# AC_mains_Sensing.net
KiCad netlist of a schematic drawn in Altium Designer
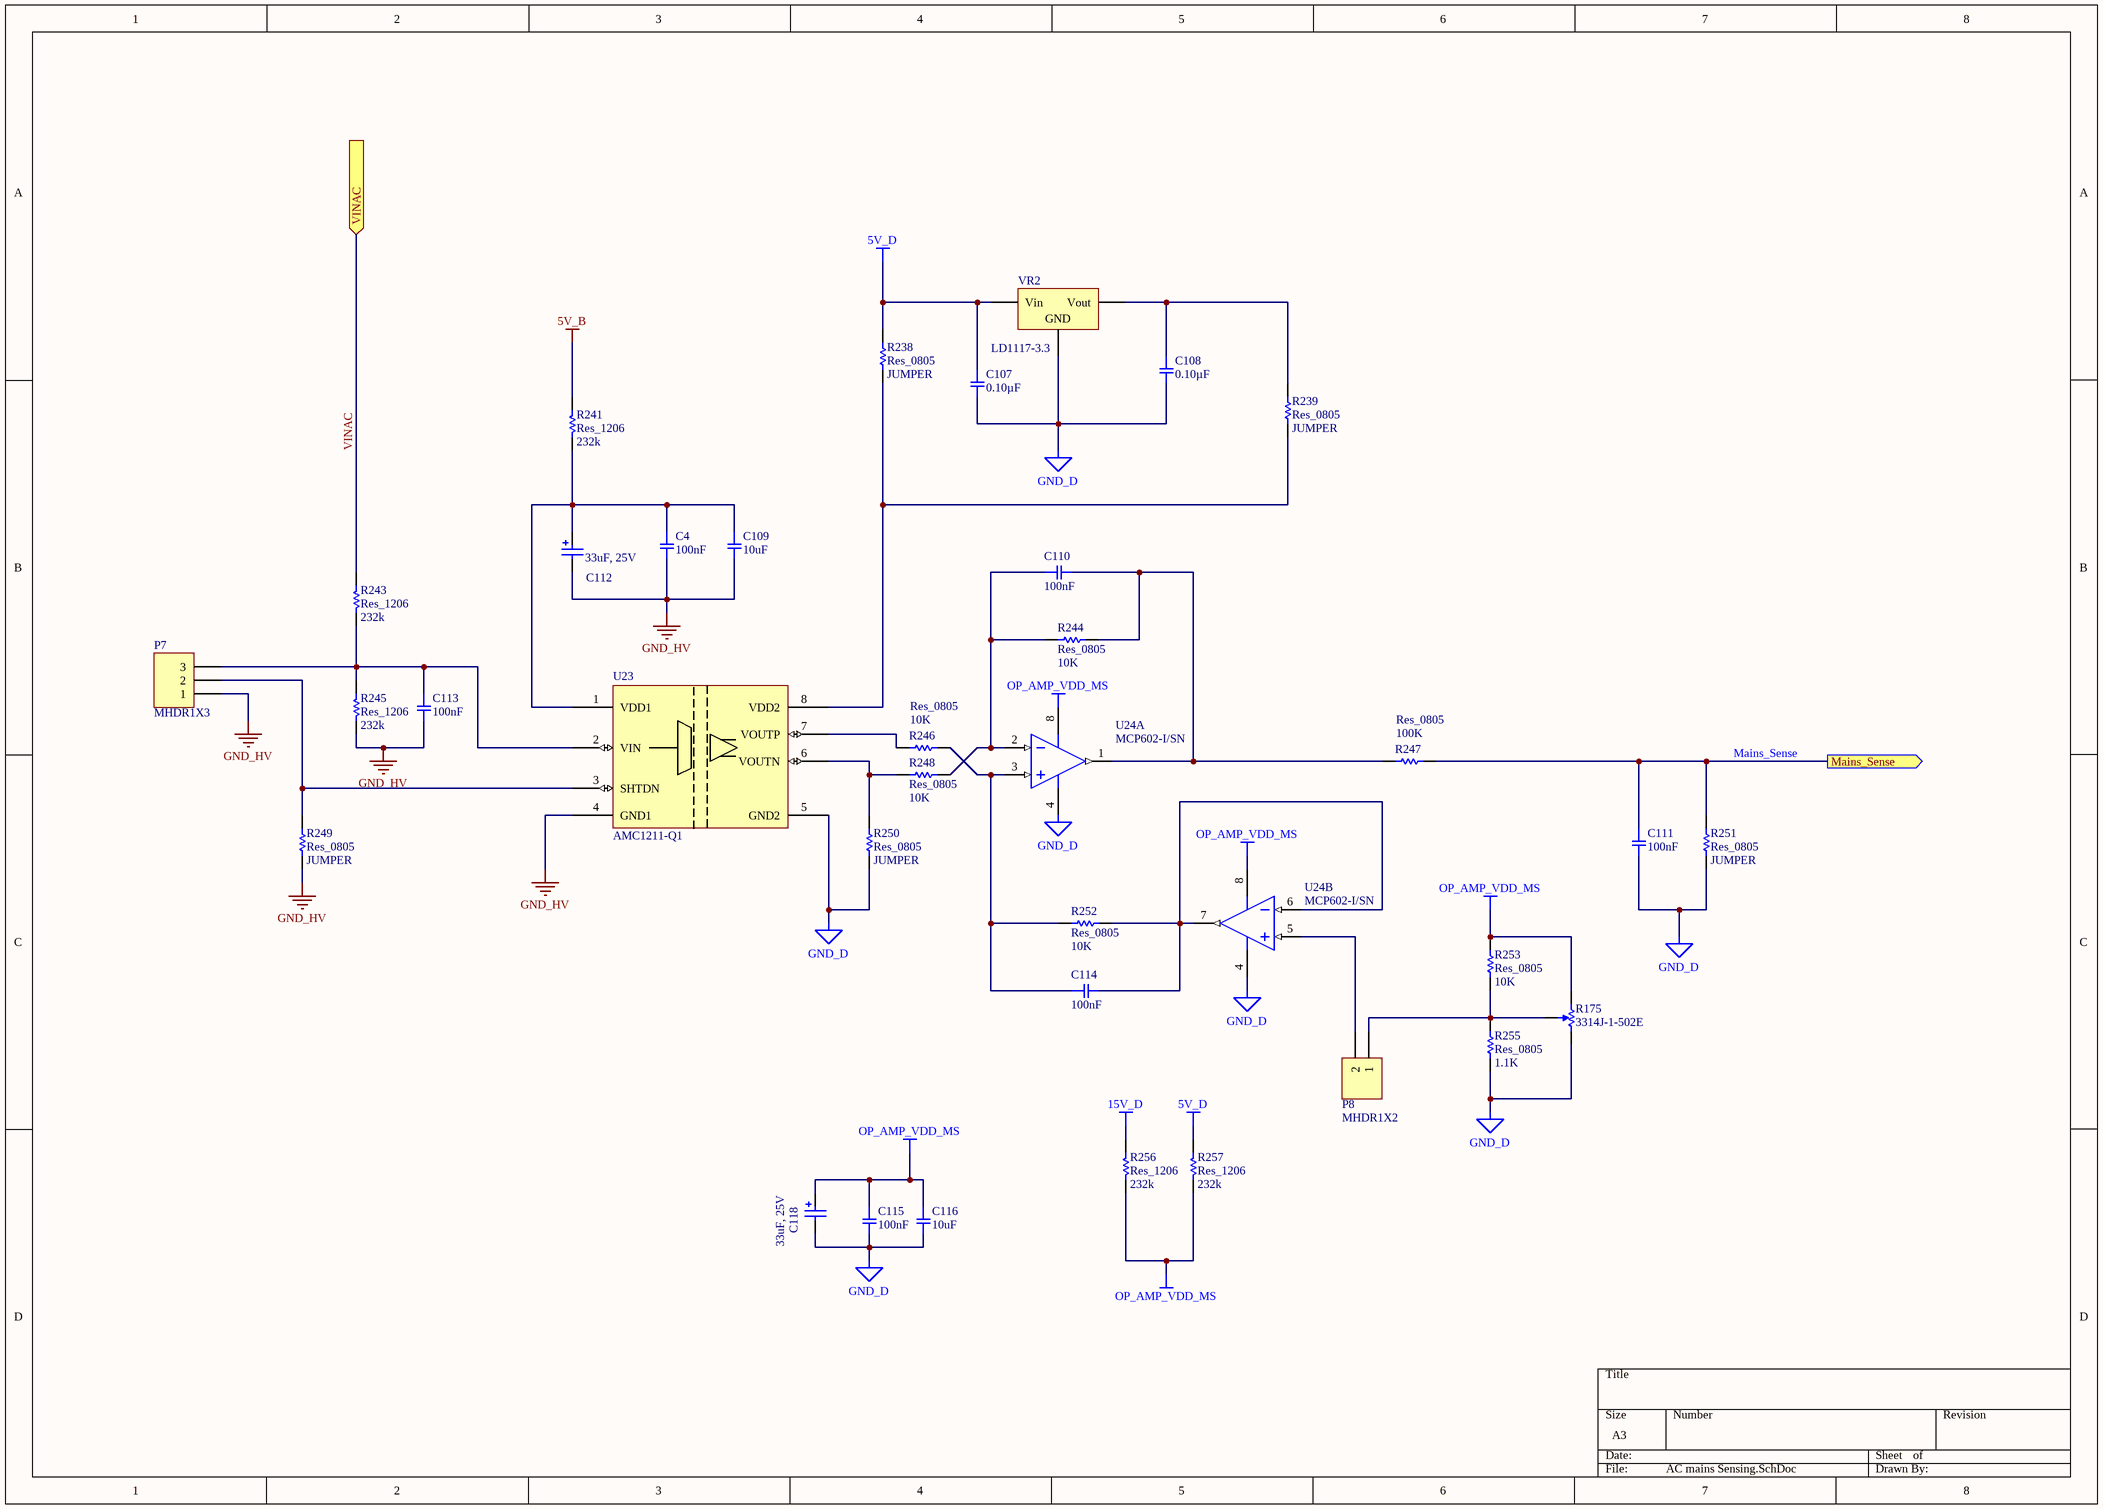
[diagram p0: AC mains Sensing.SchDoc]

(export (version "E")
  (design (tool "Eeschema 10.0.6"))
  (components
    (comp (ref "C4")
      (value "100nF")
      (footprint "SMD-0805C")
      (description "CAP CER 10000PF 250V X7T 0805")
      (fields
        (field (name "DIGI-KEY PART NUMBER") "490-13986-1-ND")
        (field (name "PART NUMBER") "GC321AD72E103KX01D")
      )
      (libsource (lib "capacitor_murata_0805") (part "GC321AD72E103KX01D"))
    )
    (comp (ref "C107")
      (value "0.10µF")
      (footprint "SMD-0805C")
      (description "CAP CER 0.1UF 50V X7R 0805")
      (fields
        (field (name "DIGI-KEY PART NUMBER") "490-11955-1-ND")
        (field (name "PART NUMBER") "GCD21BR71H104KA01L")
      )
      (libsource (lib "capacitor_murata_0805") (part "GCD21BR71H104KA01L"))
    )
    (comp (ref "C108")
      (value "0.10µF")
      (footprint "SMD-0805C")
      (description "CAP CER 0.1UF 50V X7R 0805")
      (fields
        (field (name "DIGI-KEY PART NUMBER") "490-11955-1-ND")
        (field (name "PART NUMBER") "GCD21BR71H104KA01L")
      )
      (libsource (lib "capacitor_murata_0805") (part "GCD21BR71H104KA01L"))
    )
    (comp (ref "C109")
      (value "10uF")
      (footprint "SMD-0805C")
      (description "CAP CER 10000PF 250V X7T 0805")
      (fields
        (field (name "DIGI-KEY PART NUMBER") "490-13986-1-ND")
        (field (name "PART NUMBER") "GC321AD72E103KX01D")
      )
      (libsource (lib "capacitor_murata_0805") (part "GC321AD72E103KX01D"))
    )
    (comp (ref "C110")
      (value "100nF")
      (footprint "SMD-0805C")
      (description "CAP CER 10000PF 250V X7T 0805")
      (fields
        (field (name "DIGI-KEY PART NUMBER") "490-13986-1-ND")
        (field (name "PART NUMBER") "GC321AD72E103KX01D")
      )
      (libsource (lib "capacitor_murata_0805") (part "GC321AD72E103KX01D"))
    )
    (comp (ref "C111")
      (value "100nF")
      (footprint "SMD-0805C")
      (description "CAP CER 10000PF 250V X7T 0805")
      (fields
        (field (name "DIGI-KEY PART NUMBER") "490-13986-1-ND")
        (field (name "PART NUMBER") "GC321AD72E103KX01D")
      )
      (libsource (lib "capacitor_murata_0805") (part "GC321AD72E103KX01D"))
    )
    (comp (ref "C112")
      (value "33uF, 25V")
      (footprint "WCAP-ASLL_6.3x5.5")
      (description "WCAP-ASLL SMT Aluminum Electrolytic Capacitors, D6.3mm x L5.5mm, 33uF, +/-20%, 25VDC")
      (fields (field (name "PART NUMBER") "865060443003") (field (name "PUBLISHER") "Wurth Elektronik"))
      (libsource (lib "Altium_WCAP-ASLL_SMD") (part "865060443003"))
    )
    (comp (ref "C113")
      (value "100nF")
      (footprint "SMD-0805C")
      (description "CAP CER 10000PF 250V X7T 0805")
      (fields
        (field (name "DIGI-KEY PART NUMBER") "490-13986-1-ND")
        (field (name "PART NUMBER") "GC321AD72E103KX01D")
      )
      (libsource (lib "capacitor_murata_0805") (part "GC321AD72E103KX01D"))
    )
    (comp (ref "C114")
      (value "100nF")
      (footprint "SMD-0805C")
      (description "CAP CER 10000PF 250V X7T 0805")
      (fields
        (field (name "DIGI-KEY PART NUMBER") "490-13986-1-ND")
        (field (name "PART NUMBER") "GC321AD72E103KX01D")
      )
      (libsource (lib "capacitor_murata_0805") (part "GC321AD72E103KX01D"))
    )
    (comp (ref "C115")
      (value "100nF")
      (footprint "SMD-0805C")
      (description "CAP CER 10000PF 250V X7T 0805")
      (fields
        (field (name "DIGI-KEY PART NUMBER") "490-13986-1-ND")
        (field (name "PART NUMBER") "GC321AD72E103KX01D")
      )
      (libsource (lib "capacitor_murata_0805") (part "GC321AD72E103KX01D"))
    )
    (comp (ref "C116")
      (value "10uF")
      (footprint "SMD-0805C")
      (description "CAP CER 10000PF 250V X7T 0805")
      (fields
        (field (name "DIGI-KEY PART NUMBER") "490-13986-1-ND")
        (field (name "PART NUMBER") "GC321AD72E103KX01D")
      )
      (libsource (lib "capacitor_murata_0805") (part "GC321AD72E103KX01D"))
    )
    (comp (ref "C118")
      (value "33uF, 25V")
      (footprint "WCAP-ASLL_6.3x5.5")
      (description "WCAP-ASLL SMT Aluminum Electrolytic Capacitors, D6.3mm x L5.5mm, 33uF, +/-20%, 25VDC")
      (fields (field (name "PART NUMBER") "865060443003") (field (name "PUBLISHER") "Wurth Elektronik"))
      (libsource (lib "Altium_WCAP-ASLL_SMD") (part "865060443003"))
    )
    (comp (ref "P7")
      (value "MHDR1X3")
      (footprint "MHDR1X3")
      (description "Header, 3-Pin")
      (fields (field (name "PUBLISHER") "Altium Limited"))
      (libsource (lib "Miscellaneous Connectors") (part "MHDR1X3"))
    )
    (comp (ref "P8")
      (value "MHDR1X2")
      (footprint "61900211121")
      (description "Header, 2-Pin")
      (fields (field (name "PUBLISHER") "Altium Limited"))
      (libsource (lib "Miscellaneous Connectors") (part "MHDR1X2"))
    )
    (comp (ref "R175")
      (value "3314J-1-502E")
      (footprint "BOUR-3314J-1_V")
      (fields
        (field (name "POWER") "250")
        (field (name "MANUFACTURER") "Bourns")
        (field (name "TOLERANCE") "±20%")
      )
      (libsource (lib "Altium Content Vault") (part "RES-ADJ-3_A"))
    )
    (comp (ref "R238")
      (value "Res_0805")
      (footprint "WRIS-KSKE_0805_H=0.6mm")
      (description "Resistor")
      (fields (field (name "ALTIUM_VALUE") "JUMPER") (field (name "PUBLISHER") "Altium Limited"))
      (libsource (lib "Miscellaneous Devices") (part "Res1"))
    )
    (comp (ref "R239")
      (value "Res_0805")
      (footprint "WRIS-KSKE_0805_H=0.6mm")
      (description "Resistor")
      (fields (field (name "ALTIUM_VALUE") "JUMPER") (field (name "PUBLISHER") "Altium Limited"))
      (libsource (lib "Miscellaneous Devices") (part "Res1"))
    )
    (comp (ref "R241")
      (value "Res_1206")
      (footprint "WRIS-KSKE_1206_H=0.6mm")
      (description "Resistor")
      (fields (field (name "ALTIUM_VALUE") "232k") (field (name "PUBLISHER") "Altium Limited"))
      (libsource (lib "Miscellaneous Devices") (part "Res1"))
    )
    (comp (ref "R243")
      (value "Res_1206")
      (footprint "WRIS-KSKE_1206_H=0.6mm")
      (description "Resistor")
      (fields (field (name "ALTIUM_VALUE") "232k") (field (name "PUBLISHER") "Altium Limited"))
      (libsource (lib "Miscellaneous Devices") (part "Res1"))
    )
    (comp (ref "R244")
      (value "Res_0805")
      (footprint "WRIS-KSKE_0805_H=0.6mm")
      (description "Resistor")
      (fields (field (name "ALTIUM_VALUE") "10K") (field (name "PUBLISHER") "Altium Limited"))
      (libsource (lib "Miscellaneous Devices") (part "Res1"))
    )
    (comp (ref "R245")
      (value "Res_1206")
      (footprint "WRIS-KSKE_1206_H=0.6mm")
      (description "Resistor")
      (fields (field (name "ALTIUM_VALUE") "232k") (field (name "PUBLISHER") "Altium Limited"))
      (libsource (lib "Miscellaneous Devices") (part "Res1"))
    )
    (comp (ref "R246")
      (value "Res_0805")
      (footprint "WRIS-KSKE_0805_H=0.6mm")
      (description "Resistor")
      (fields (field (name "ALTIUM_VALUE") "10K") (field (name "PUBLISHER") "Altium Limited"))
      (libsource (lib "Miscellaneous Devices") (part "Res1"))
    )
    (comp (ref "R247")
      (value "Res_0805")
      (footprint "WRIS-KSKE_0805_H=0.6mm")
      (description "Resistor")
      (fields (field (name "ALTIUM_VALUE") "100K") (field (name "PUBLISHER") "Altium Limited"))
      (libsource (lib "Miscellaneous Devices") (part "Res1"))
    )
    (comp (ref "R248")
      (value "Res_0805")
      (footprint "WRIS-KSKE_0805_H=0.6mm")
      (description "Resistor")
      (fields (field (name "ALTIUM_VALUE") "10K") (field (name "PUBLISHER") "Altium Limited"))
      (libsource (lib "Miscellaneous Devices") (part "Res1"))
    )
    (comp (ref "R249")
      (value "Res_0805")
      (footprint "WRIS-KSKE_0805_H=0.6mm")
      (description "Resistor")
      (fields (field (name "ALTIUM_VALUE") "JUMPER") (field (name "PUBLISHER") "Altium Limited"))
      (libsource (lib "Miscellaneous Devices") (part "Res1"))
    )
    (comp (ref "R250")
      (value "Res_0805")
      (footprint "WRIS-KSKE_0805_H=0.6mm")
      (description "Resistor")
      (fields (field (name "ALTIUM_VALUE") "JUMPER") (field (name "PUBLISHER") "Altium Limited"))
      (libsource (lib "Miscellaneous Devices") (part "Res1"))
    )
    (comp (ref "R251")
      (value "Res_0805")
      (footprint "WRIS-KSKE_0805_H=0.6mm")
      (description "Resistor")
      (fields (field (name "ALTIUM_VALUE") "JUMPER") (field (name "PUBLISHER") "Altium Limited"))
      (libsource (lib "Miscellaneous Devices") (part "Res1"))
    )
    (comp (ref "R252")
      (value "Res_0805")
      (footprint "WRIS-KSKE_0805_H=0.6mm")
      (description "Resistor")
      (fields (field (name "ALTIUM_VALUE") "10K") (field (name "PUBLISHER") "Altium Limited"))
      (libsource (lib "Miscellaneous Devices") (part "Res1"))
    )
    (comp (ref "R253")
      (value "Res_0805")
      (footprint "WRIS-KSKE_0805_H=0.6mm")
      (description "Resistor")
      (fields (field (name "ALTIUM_VALUE") "10K") (field (name "PUBLISHER") "Altium Limited"))
      (libsource (lib "Miscellaneous Devices") (part "Res1"))
    )
    (comp (ref "R255")
      (value "Res_0805")
      (footprint "WRIS-KSKE_0805_H=0.6mm")
      (description "Resistor")
      (fields (field (name "ALTIUM_VALUE") "1.1K") (field (name "PUBLISHER") "Altium Limited"))
      (libsource (lib "Miscellaneous Devices") (part "Res1"))
    )
    (comp (ref "R256")
      (value "Res_1206")
      (footprint "WRIS-KSKE_1206_H=0.6mm")
      (description "Resistor")
      (fields (field (name "ALTIUM_VALUE") "232k") (field (name "PUBLISHER") "Altium Limited"))
      (libsource (lib "Miscellaneous Devices") (part "Res1"))
    )
    (comp (ref "R257")
      (value "Res_1206")
      (footprint "WRIS-KSKE_1206_H=0.6mm")
      (description "Resistor")
      (fields (field (name "ALTIUM_VALUE") "232k") (field (name "PUBLISHER") "Altium Limited"))
      (libsource (lib "Miscellaneous Devices") (part "Res1"))
    )
    (comp (ref "U23")
      (value "AMC1211-Q1")
      (footprint "SOIC127P570X175_HS-9N - No Thermal")
      (libsource (lib "PFC_Stage") (part "AMC1211-Q1"))
    )
    (comp (ref "U24")
      (value "MCP602-I/SN")
      (footprint "SOIC127P570X175_HS-9N - No Thermal")
      (description "2.7V to 6.0V Single Supply CMOS Operational Amplifier, 8-Pin SOIC, Industrial Temperature")
      (libsource (lib "Power Board UCC28951") (part "MCP602_2"))
    )
    (comp (ref "VR2")
      (value "LD1117-3.3")
      (footprint "SOT230P700X180-4N")
      (description "Voltage Regulator")
      (fields (field (name "PUBLISHER") "Altium Limited"))
      (libsource (lib "PFC_Stage") (part "LD117-3.3"))
    )
  )
  (nets
    (net (code "1") (name "/Mains_Sense") (class "Default")
      (node (ref "C111") (pin "1") (pinfunction "1_1") (pintype "passive"))
      (node (ref "R247") (pin "2") (pinfunction "2_2") (pintype "passive"))
      (node (ref "R251") (pin "1") (pinfunction "1_1") (pintype "passive"))
    )
    (net (code "2") (name "/VINAC") (class "Default")
      (node (ref "R243") (pin "2") (pinfunction "2_2") (pintype "passive"))
    )
    (net (code "3") (name "5V_B") (class "Default")
      (node (ref "R241") (pin "2") (pinfunction "2_2") (pintype "passive"))
    )
    (net (code "4") (name "5V_D") (class "Default")
      (node (ref "C107") (pin "1") (pinfunction "1_1") (pintype "passive"))
      (node (ref "R238") (pin "1") (pinfunction "1_1") (pintype "passive"))
      (node (ref "R257") (pin "2") (pinfunction "2_2") (pintype "passive"))
      (node (ref "VR2") (pin "3") (pinfunction "Vin_3") (pintype "passive"))
    )
    (net (code "5") (name "15V_D") (class "Default")
      (node (ref "R256") (pin "2") (pinfunction "2_2") (pintype "passive"))
    )
    (net (code "6") (name "GND_D") (class "Default")
      (node (ref "C107") (pin "2") (pinfunction "2_2") (pintype "passive"))
      (node (ref "C108") (pin "2") (pinfunction "2_2") (pintype "passive"))
      (node (ref "C111") (pin "2") (pinfunction "2_2") (pintype "passive"))
      (node (ref "C115") (pin "2") (pinfunction "2_2") (pintype "passive"))
      (node (ref "C116") (pin "2") (pinfunction "2_2") (pintype "passive"))
      (node (ref "C118") (pin "1") (pinfunction "N_1") (pintype "passive"))
      (node (ref "R175") (pin "3") (pinfunction "3_3") (pintype "passive"))
      (node (ref "R250") (pin "2") (pinfunction "2_2") (pintype "passive"))
      (node (ref "R251") (pin "2") (pinfunction "2_2") (pintype "passive"))
      (node (ref "R255") (pin "2") (pinfunction "2_2") (pintype "passive"))
      (node (ref "U23") (pin "5") (pinfunction "GND2_5") (pintype "power_in"))
      (node (ref "U24") (pin "4") (pinfunction "VSS_4") (pintype "power_in"))
      (node (ref "VR2") (pin "1") (pinfunction "GND_1") (pintype "passive"))
    )
    (net (code "7") (name "GND_HV") (class "Default")
      (node (ref "C109") (pin "2") (pinfunction "2_2") (pintype "passive"))
      (node (ref "C112") (pin "1") (pinfunction "N_1") (pintype "passive"))
      (node (ref "C113") (pin "2") (pinfunction "2_2") (pintype "passive"))
      (node (ref "C4") (pin "2") (pinfunction "2_2") (pintype "passive"))
      (node (ref "P7") (pin "1") (pinfunction "1_1") (pintype "passive"))
      (node (ref "R245") (pin "1") (pinfunction "1_1") (pintype "passive"))
      (node (ref "R249") (pin "2") (pinfunction "2_2") (pintype "passive"))
      (node (ref "U23") (pin "4") (pinfunction "GND1_4") (pintype "power_in"))
    )
    (net (code "8") (name "Net-(C112-P)") (class "Default")
      (node (ref "C109") (pin "1") (pinfunction "1_1") (pintype "passive"))
      (node (ref "C112") (pin "2") (pinfunction "P_2") (pintype "passive"))
      (node (ref "C4") (pin "1") (pinfunction "1_1") (pintype "passive"))
      (node (ref "R241") (pin "1") (pinfunction "1_1") (pintype "passive"))
      (node (ref "U23") (pin "1") (pinfunction "VDD1_1") (pintype "power_in"))
    )
    (net (code "9") (name "Net-(P8-Pad1)") (class "Default")
      (node (ref "P8") (pin "1") (pinfunction "1_1") (pintype "passive"))
      (node (ref "R175") (pin "2") (pinfunction "2_2") (pintype "passive"))
      (node (ref "R253") (pin "2") (pinfunction "2_2") (pintype "passive"))
      (node (ref "R255") (pin "1") (pinfunction "1_1") (pintype "passive"))
    )
    (net (code "10") (name "Net-(U23-SHTDN)") (class "Default")
      (node (ref "P7") (pin "2") (pinfunction "2_2") (pintype "passive"))
      (node (ref "R249") (pin "1") (pinfunction "1_1") (pintype "passive"))
      (node (ref "U23") (pin "3") (pinfunction "SHTDN_3") (pintype "bidirectional"))
    )
    (net (code "11") (name "Net-(U23-VDD2)") (class "Default")
      (node (ref "R238") (pin "2") (pinfunction "2_2") (pintype "passive"))
      (node (ref "R239") (pin "2") (pinfunction "2_2") (pintype "passive"))
      (node (ref "U23") (pin "8") (pinfunction "VDD2_8") (pintype "power_in"))
    )
    (net (code "12") (name "Net-(U23-VIN)") (class "Default")
      (node (ref "C113") (pin "1") (pinfunction "1_1") (pintype "passive"))
      (node (ref "P7") (pin "3") (pinfunction "3_3") (pintype "passive"))
      (node (ref "R243") (pin "1") (pinfunction "1_1") (pintype "passive"))
      (node (ref "R245") (pin "2") (pinfunction "2_2") (pintype "passive"))
      (node (ref "U23") (pin "2") (pinfunction "VIN_2") (pintype "bidirectional"))
    )
    (net (code "13") (name "Net-(U23-VOUTN)") (class "Default")
      (node (ref "R248") (pin "1") (pinfunction "1_1") (pintype "passive"))
      (node (ref "R250") (pin "1") (pinfunction "1_1") (pintype "passive"))
      (node (ref "U23") (pin "6") (pinfunction "VOUTN_6") (pintype "bidirectional"))
    )
    (net (code "14") (name "Net-(U23-VOUTP)") (class "Default")
      (node (ref "R246") (pin "1") (pinfunction "1_1") (pintype "passive"))
      (node (ref "U23") (pin "7") (pinfunction "VOUTP_7") (pintype "bidirectional"))
    )
    (net (code "15") (name "Net-(U24A-VINA+)") (class "Default")
      (node (ref "C114") (pin "1") (pinfunction "1_1") (pintype "passive"))
      (node (ref "R246") (pin "2") (pinfunction "2_2") (pintype "passive"))
      (node (ref "R252") (pin "1") (pinfunction "1_1") (pintype "passive"))
      (node (ref "U24") (pin "3") (pinfunction "VINA+_3") (pintype "input"))
    )
    (net (code "16") (name "Net-(U24A-VINA-)") (class "Default")
      (node (ref "C110") (pin "1") (pinfunction "1_1") (pintype "passive"))
      (node (ref "R244") (pin "1") (pinfunction "1_1") (pintype "passive"))
      (node (ref "R248") (pin "2") (pinfunction "2_2") (pintype "passive"))
      (node (ref "U24") (pin "2") (pinfunction "VINA-_2") (pintype "input"))
    )
    (net (code "17") (name "Net-(U24A-VOUTA)") (class "Default")
      (node (ref "C110") (pin "2") (pinfunction "2_2") (pintype "passive"))
      (node (ref "R244") (pin "2") (pinfunction "2_2") (pintype "passive"))
      (node (ref "R247") (pin "1") (pinfunction "1_1") (pintype "passive"))
      (node (ref "U24") (pin "1") (pinfunction "VOUTA_1") (pintype "output"))
    )
    (net (code "18") (name "Net-(U24B-VINB+)") (class "Default")
      (node (ref "P8") (pin "2") (pinfunction "2_2") (pintype "passive"))
      (node (ref "U24") (pin "5") (pinfunction "VINB+_5") (pintype "input"))
    )
    (net (code "19") (name "Net-(U24B-VINB-)") (class "Default")
      (node (ref "C114") (pin "2") (pinfunction "2_2") (pintype "passive"))
      (node (ref "R252") (pin "2") (pinfunction "2_2") (pintype "passive"))
      (node (ref "U24") (pin "6") (pinfunction "VINB-_6") (pintype "input"))
      (node (ref "U24") (pin "7") (pinfunction "VOUTB_7") (pintype "output"))
    )
    (net (code "20") (name "Net-(VR2-Vout)") (class "Default")
      (node (ref "C108") (pin "1") (pinfunction "1_1") (pintype "passive"))
      (node (ref "R239") (pin "1") (pinfunction "1_1") (pintype "passive"))
      (node (ref "VR2") (pin "2") (pinfunction "Vout_2") (pintype "passive"))
    )
    (net (code "21") (name "OP_AMP_VDD_MS") (class "Default")
      (node (ref "C115") (pin "1") (pinfunction "1_1") (pintype "passive"))
      (node (ref "C116") (pin "1") (pinfunction "1_1") (pintype "passive"))
      (node (ref "C118") (pin "2") (pinfunction "P_2") (pintype "passive"))
      (node (ref "R175") (pin "1") (pinfunction "1_1") (pintype "passive"))
      (node (ref "R253") (pin "1") (pinfunction "1_1") (pintype "passive"))
      (node (ref "R256") (pin "1") (pinfunction "1_1") (pintype "passive"))
      (node (ref "R257") (pin "1") (pinfunction "1_1") (pintype "passive"))
      (node (ref "U24") (pin "8") (pinfunction "VDD_8") (pintype "power_in"))
    )
  )
)
